# LEDS_DISP.net
KiCad netlist of a schematic drawn in Altium Designer
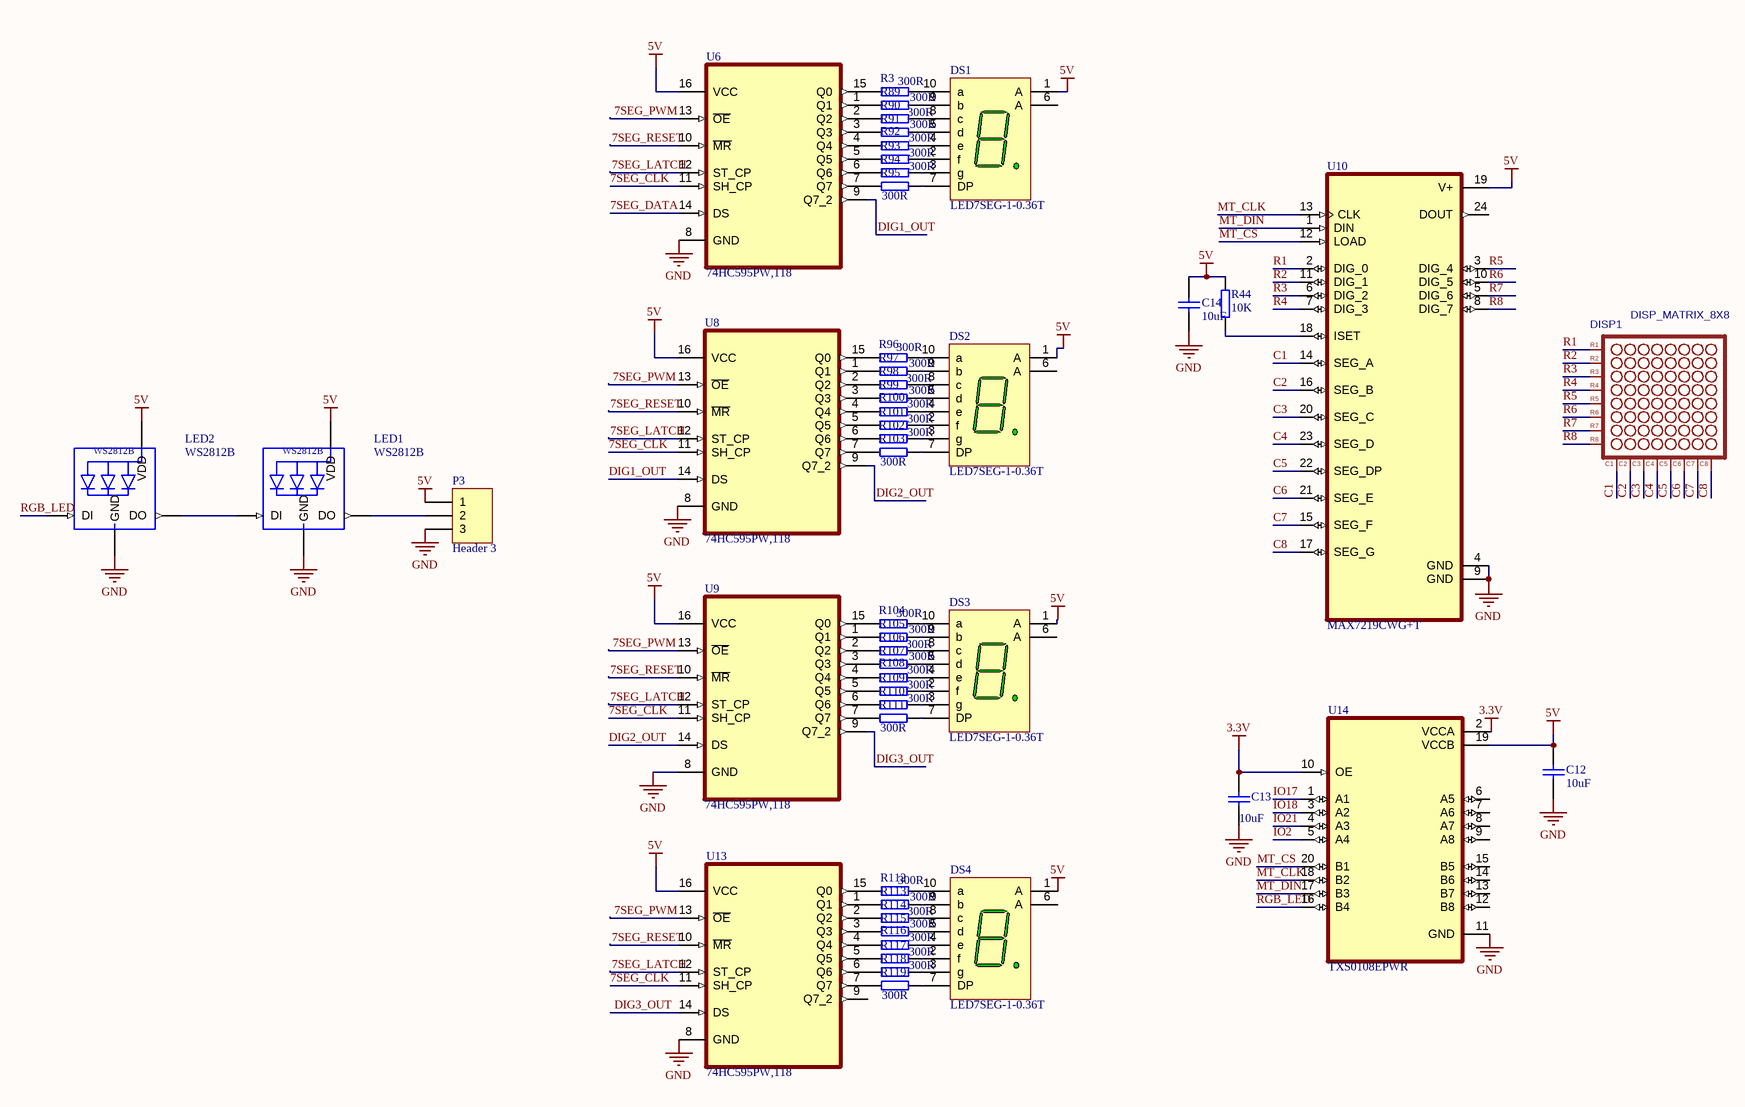
[diagram p0: LEDS_DISP.SchDoc]

(export (version "E")
  (design (tool "Eeschema 10.0.6"))
  (components
    (comp (ref "C12")
      (value "10uF")
      (footprint "CAPC1608X90N")
      (description "CAP SM 0603 X5R 10uF 10%")
      (fields (field (name "TOLERANCE") "±10%") (field (name "Comment") "Cap Semi"))
      (libsource (lib "electronpowered") (part "CAP-SM-0603-X5R-10uF"))
    )
    (comp (ref "C13")
      (value "10uF")
      (footprint "CAPC1608X90N")
      (description "CAP SM 0603 X5R 10uF 10%")
      (fields (field (name "TOLERANCE") "±10%") (field (name "Comment") "Cap Semi"))
      (libsource (lib "electronpowered") (part "CAP-SM-0603-X5R-10uF"))
    )
    (comp (ref "C14")
      (value "10uF")
      (footprint "CAPC1608X90N")
      (description "CAP SM 0603 X5R 10uF 10%")
      (fields (field (name "TOLERANCE") "±10%") (field (name "Comment") "Cap Semi"))
      (libsource (lib "electronpowered") (part "CAP-SM-0603-X5R-10uF"))
    )
    (comp (ref "DISP1")
      (value "DISP_MATRIX_8X8")
      (footprint "DISP_8X8_MATRIX_2020")
      (fields (field (name "BOM_MANUFACTURER PART") "?") (field (name "CONTRIBUTOR") "DangerousPrototype"))
      (libsource (lib "ledmatrix") (part "DISP_MATRIX_8X8"))
    )
    (comp (ref "DS1")
      (value "LED7SEG-1-0.36T")
      (footprint "LED7SEG-1-0.36T")
      (description "7.6 mm Micro Bright Green 7-Segment Display: CA, RH DP")
      (fields (field (name "PUBLISHER") "Altium Limited"))
      (libsource (lib "My Library") (part "LED7SEG-1-0.36T"))
    )
    (comp (ref "DS2")
      (value "LED7SEG-1-0.36T")
      (footprint "LED7SEG-1-0.36T")
      (description "7.6 mm Micro Bright Green 7-Segment Display: CA, RH DP")
      (fields (field (name "PUBLISHER") "Altium Limited"))
      (libsource (lib "My Library") (part "LED7SEG-1-0.36T"))
    )
    (comp (ref "DS3")
      (value "LED7SEG-1-0.36T")
      (footprint "LED7SEG-1-0.36T")
      (description "7.6 mm Micro Bright Green 7-Segment Display: CA, RH DP")
      (fields (field (name "PUBLISHER") "Altium Limited"))
      (libsource (lib "My Library") (part "LED7SEG-1-0.36T"))
    )
    (comp (ref "DS4")
      (value "LED7SEG-1-0.36T")
      (footprint "LED7SEG-1-0.36T")
      (description "7.6 mm Micro Bright Green 7-Segment Display: CA, RH DP")
      (fields (field (name "PUBLISHER") "Altium Limited"))
      (libsource (lib "My Library") (part "LED7SEG-1-0.36T"))
    )
    (comp (ref "LED1")
      (value "WS2812B")
      (footprint "WS2812B")
      (description "Raspberry Pi HAT _40 pin_ Wheeled Robotics Kit")
      (fields (field (name "MF") "SparkFun Electronics"))
      (libsource (lib "WIle_dev_kit") (part "WS2812B"))
    )
    (comp (ref "LED2")
      (value "WS2812B")
      (footprint "WS2812B")
      (description "Raspberry Pi HAT _40 pin_ Wheeled Robotics Kit")
      (fields (field (name "MF") "SparkFun Electronics"))
      (libsource (lib "WIle_dev_kit") (part "WS2812B"))
    )
    (comp (ref "P3")
      (value "Header 3")
      (footprint "HDR1X3")
      (description "Header, 3-Pin")
      (fields (field (name "PUBLISHER") "Altium Limited"))
      (libsource (lib "WIle_dev_kit") (part "Header 3"))
    )
    (comp (ref "R3")
      (value "300R")
      (footprint "RESC1608N_ZERO")
      (description "RES SM 0603 300R")
      (fields (field (name "Comment") "Resistor"))
      (libsource (lib "electronpowered") (part "RES-SM-0603-10K"))
    )
    (comp (ref "R44")
      (value "10K")
      (footprint "RESC1608N_ZERO")
      (description "RES SM 0603 10K")
      (fields (field (name "Comment") "Resistor"))
      (libsource (lib "electronpowered") (part "RES-SM-0603-10K"))
    )
    (comp (ref "R89")
      (value "300R")
      (footprint "RESC1608N_ZERO")
      (description "RES SM 0603 300R")
      (fields (field (name "Comment") "Resistor"))
      (libsource (lib "electronpowered") (part "RES-SM-0603-10K"))
    )
    (comp (ref "R90")
      (value "300R")
      (footprint "RESC1608N_ZERO")
      (description "RES SM 0603 300R")
      (fields (field (name "Comment") "Resistor"))
      (libsource (lib "electronpowered") (part "RES-SM-0603-10K"))
    )
    (comp (ref "R91")
      (value "300R")
      (footprint "RESC1608N_ZERO")
      (description "RES SM 0603 300R")
      (fields (field (name "Comment") "Resistor"))
      (libsource (lib "electronpowered") (part "RES-SM-0603-10K"))
    )
    (comp (ref "R92")
      (value "300R")
      (footprint "RESC1608N_ZERO")
      (description "RES SM 0603 300R")
      (fields (field (name "Comment") "Resistor"))
      (libsource (lib "electronpowered") (part "RES-SM-0603-10K"))
    )
    (comp (ref "R93")
      (value "300R")
      (footprint "RESC1608N_ZERO")
      (description "RES SM 0603 300R")
      (fields (field (name "Comment") "Resistor"))
      (libsource (lib "electronpowered") (part "RES-SM-0603-10K"))
    )
    (comp (ref "R94")
      (value "300R")
      (footprint "RESC1608N_ZERO")
      (description "RES SM 0603 300R")
      (fields (field (name "Comment") "Resistor"))
      (libsource (lib "electronpowered") (part "RES-SM-0603-10K"))
    )
    (comp (ref "R95")
      (value "300R")
      (footprint "RESC1608N_ZERO")
      (description "RES SM 0603 300R")
      (fields (field (name "Comment") "Resistor"))
      (libsource (lib "electronpowered") (part "RES-SM-0603-10K"))
    )
    (comp (ref "R96")
      (value "300R")
      (footprint "RESC1608N_ZERO")
      (description "RES SM 0603 300R")
      (fields (field (name "Comment") "Resistor"))
      (libsource (lib "electronpowered") (part "RES-SM-0603-10K"))
    )
    (comp (ref "R97")
      (value "300R")
      (footprint "RESC1608N_ZERO")
      (description "RES SM 0603 300R")
      (fields (field (name "Comment") "Resistor"))
      (libsource (lib "electronpowered") (part "RES-SM-0603-10K"))
    )
    (comp (ref "R98")
      (value "300R")
      (footprint "RESC1608N_ZERO")
      (description "RES SM 0603 300R")
      (fields (field (name "Comment") "Resistor"))
      (libsource (lib "electronpowered") (part "RES-SM-0603-10K"))
    )
    (comp (ref "R99")
      (value "300R")
      (footprint "RESC1608N_ZERO")
      (description "RES SM 0603 300R")
      (fields (field (name "Comment") "Resistor"))
      (libsource (lib "electronpowered") (part "RES-SM-0603-10K"))
    )
    (comp (ref "R100")
      (value "300R")
      (footprint "RESC1608N_ZERO")
      (description "RES SM 0603 300R")
      (fields (field (name "Comment") "Resistor"))
      (libsource (lib "electronpowered") (part "RES-SM-0603-10K"))
    )
    (comp (ref "R101")
      (value "300R")
      (footprint "RESC1608N_ZERO")
      (description "RES SM 0603 300R")
      (fields (field (name "Comment") "Resistor"))
      (libsource (lib "electronpowered") (part "RES-SM-0603-10K"))
    )
    (comp (ref "R102")
      (value "300R")
      (footprint "RESC1608N_ZERO")
      (description "RES SM 0603 300R")
      (fields (field (name "Comment") "Resistor"))
      (libsource (lib "electronpowered") (part "RES-SM-0603-10K"))
    )
    (comp (ref "R103")
      (value "300R")
      (footprint "RESC1608N_ZERO")
      (description "RES SM 0603 300R")
      (fields (field (name "Comment") "Resistor"))
      (libsource (lib "electronpowered") (part "RES-SM-0603-10K"))
    )
    (comp (ref "R104")
      (value "300R")
      (footprint "RESC1608N_ZERO")
      (description "RES SM 0603 300R")
      (fields (field (name "Comment") "Resistor"))
      (libsource (lib "electronpowered") (part "RES-SM-0603-10K"))
    )
    (comp (ref "R105")
      (value "300R")
      (footprint "RESC1608N_ZERO")
      (description "RES SM 0603 300R")
      (fields (field (name "Comment") "Resistor"))
      (libsource (lib "electronpowered") (part "RES-SM-0603-10K"))
    )
    (comp (ref "R106")
      (value "300R")
      (footprint "RESC1608N_ZERO")
      (description "RES SM 0603 300R")
      (fields (field (name "Comment") "Resistor"))
      (libsource (lib "electronpowered") (part "RES-SM-0603-10K"))
    )
    (comp (ref "R107")
      (value "300R")
      (footprint "RESC1608N_ZERO")
      (description "RES SM 0603 300R")
      (fields (field (name "Comment") "Resistor"))
      (libsource (lib "electronpowered") (part "RES-SM-0603-10K"))
    )
    (comp (ref "R108")
      (value "300R")
      (footprint "RESC1608N_ZERO")
      (description "RES SM 0603 300R")
      (fields (field (name "Comment") "Resistor"))
      (libsource (lib "electronpowered") (part "RES-SM-0603-10K"))
    )
    (comp (ref "R109")
      (value "300R")
      (footprint "RESC1608N_ZERO")
      (description "RES SM 0603 300R")
      (fields (field (name "Comment") "Resistor"))
      (libsource (lib "electronpowered") (part "RES-SM-0603-10K"))
    )
    (comp (ref "R110")
      (value "300R")
      (footprint "RESC1608N_ZERO")
      (description "RES SM 0603 300R")
      (fields (field (name "Comment") "Resistor"))
      (libsource (lib "electronpowered") (part "RES-SM-0603-10K"))
    )
    (comp (ref "R111")
      (value "300R")
      (footprint "RESC1608N_ZERO")
      (description "RES SM 0603 300R")
      (fields (field (name "Comment") "Resistor"))
      (libsource (lib "electronpowered") (part "RES-SM-0603-10K"))
    )
    (comp (ref "R112")
      (value "300R")
      (footprint "RESC1608N_ZERO")
      (description "RES SM 0603 300R")
      (fields (field (name "Comment") "Resistor"))
      (libsource (lib "electronpowered") (part "RES-SM-0603-10K"))
    )
    (comp (ref "R113")
      (value "300R")
      (footprint "RESC1608N_ZERO")
      (description "RES SM 0603 300R")
      (fields (field (name "Comment") "Resistor"))
      (libsource (lib "electronpowered") (part "RES-SM-0603-10K"))
    )
    (comp (ref "R114")
      (value "300R")
      (footprint "RESC1608N_ZERO")
      (description "RES SM 0603 300R")
      (fields (field (name "Comment") "Resistor"))
      (libsource (lib "electronpowered") (part "RES-SM-0603-10K"))
    )
    (comp (ref "R115")
      (value "300R")
      (footprint "RESC1608N_ZERO")
      (description "RES SM 0603 300R")
      (fields (field (name "Comment") "Resistor"))
      (libsource (lib "electronpowered") (part "RES-SM-0603-10K"))
    )
    (comp (ref "R116")
      (value "300R")
      (footprint "RESC1608N_ZERO")
      (description "RES SM 0603 300R")
      (fields (field (name "Comment") "Resistor"))
      (libsource (lib "electronpowered") (part "RES-SM-0603-10K"))
    )
    (comp (ref "R117")
      (value "300R")
      (footprint "RESC1608N_ZERO")
      (description "RES SM 0603 300R")
      (fields (field (name "Comment") "Resistor"))
      (libsource (lib "electronpowered") (part "RES-SM-0603-10K"))
    )
    (comp (ref "R118")
      (value "300R")
      (footprint "RESC1608N_ZERO")
      (description "RES SM 0603 300R")
      (fields (field (name "Comment") "Resistor"))
      (libsource (lib "electronpowered") (part "RES-SM-0603-10K"))
    )
    (comp (ref "R119")
      (value "300R")
      (footprint "RESC1608N_ZERO")
      (description "RES SM 0603 300R")
      (fields (field (name "Comment") "Resistor"))
      (libsource (lib "electronpowered") (part "RES-SM-0603-10K"))
    )
    (comp (ref "U6")
      (value "74HC595PW,118")
      (footprint "SOP65P640X110-16N")
      (description "Shift Shift Register 1 Element 8 Bit 16-TSSOP")
      (fields (field (name "MF") "Nexperia USA"))
      (libsource (lib "74HC595PW_118") (part "74HC595PW,118"))
    )
    (comp (ref "U8")
      (value "74HC595PW,118")
      (footprint "SOP65P640X110-16N")
      (description "Shift Shift Register 1 Element 8 Bit 16-TSSOP")
      (fields (field (name "MF") "Nexperia USA"))
      (libsource (lib "74HC595PW_118") (part "74HC595PW,118"))
    )
    (comp (ref "U9")
      (value "74HC595PW,118")
      (footprint "SOP65P640X110-16N")
      (description "Shift Shift Register 1 Element 8 Bit 16-TSSOP")
      (fields (field (name "MF") "Nexperia USA"))
      (libsource (lib "74HC595PW_118") (part "74HC595PW,118"))
    )
    (comp (ref "U10")
      (value "MAX7219CWG+T")
      (footprint "SOIC127P1032X265-24N")
      (description "LED Driver 64 Segment 330000uA Supply Current 24-Pin SOIC W T/R")
      (fields (field (name "MF") "Maxim Integrated Products"))
      (libsource (lib "MAX7219CWG_T") (part "MAX7219CWG+T"))
    )
    (comp (ref "U13")
      (value "74HC595PW,118")
      (footprint "SOP65P640X110-16N")
      (description "Shift Shift Register 1 Element 8 Bit 16-TSSOP")
      (fields (field (name "MF") "Nexperia USA"))
      (libsource (lib "74HC595PW_118") (part "74HC595PW,118"))
    )
    (comp (ref "U14")
      (value "TXS0108EPWR")
      (footprint "SOP65P640X120-20N")
      (description "8-bit bidirectional voltage-level shifter for open-drain and push-pull application")
      (fields (field (name "MF") "Texas Instruments"))
      (libsource (lib "TXS0108EPWR") (part "TXS0108EPWR"))
    )
  )
  (nets
    (net (code "1") (name "/7SEG_CLK") (class "Default")
      (node (ref "U13") (pin "11") (pinfunction "SH_CP_11") (pintype "input"))
      (node (ref "U6") (pin "11") (pinfunction "SH_CP_11") (pintype "input"))
      (node (ref "U8") (pin "11") (pinfunction "SH_CP_11") (pintype "input"))
      (node (ref "U9") (pin "11") (pinfunction "SH_CP_11") (pintype "input"))
    )
    (net (code "2") (name "/7SEG_DATA") (class "Default")
      (node (ref "U6") (pin "14") (pinfunction "DS_14") (pintype "input"))
    )
    (net (code "3") (name "/7SEG_LATCH") (class "Default")
      (node (ref "U13") (pin "12") (pinfunction "ST_CP_12") (pintype "input"))
      (node (ref "U6") (pin "12") (pinfunction "ST_CP_12") (pintype "input"))
      (node (ref "U8") (pin "12") (pinfunction "ST_CP_12") (pintype "input"))
      (node (ref "U9") (pin "12") (pinfunction "ST_CP_12") (pintype "input"))
    )
    (net (code "4") (name "/7SEG_PWM") (class "Default")
      (node (ref "U13") (pin "13") (pinfunction "~{OE}_13") (pintype "input"))
      (node (ref "U6") (pin "13") (pinfunction "~{OE}_13") (pintype "input"))
      (node (ref "U8") (pin "13") (pinfunction "~{OE}_13") (pintype "input"))
      (node (ref "U9") (pin "13") (pinfunction "~{OE}_13") (pintype "input"))
    )
    (net (code "5") (name "/7SEG_RESET") (class "Default")
      (node (ref "U13") (pin "10") (pinfunction "~{MR}_10") (pintype "input"))
      (node (ref "U6") (pin "10") (pinfunction "~{MR}_10") (pintype "input"))
      (node (ref "U8") (pin "10") (pinfunction "~{MR}_10") (pintype "input"))
      (node (ref "U9") (pin "10") (pinfunction "~{MR}_10") (pintype "input"))
    )
    (net (code "6") (name "/C1") (class "Default")
      (node (ref "DISP1") (pin "13") (pinfunction "C1_13") (pintype "passive"))
      (node (ref "U10") (pin "14") (pinfunction "SEG_A_14") (pintype "bidirectional"))
    )
    (net (code "7") (name "/C2") (class "Default")
      (node (ref "DISP1") (pin "3") (pinfunction "C2_3") (pintype "passive"))
      (node (ref "U10") (pin "16") (pinfunction "SEG_B_16") (pintype "bidirectional"))
    )
    (net (code "8") (name "/C3") (class "Default")
      (node (ref "DISP1") (pin "4") (pinfunction "C3_4") (pintype "passive"))
      (node (ref "U10") (pin "20") (pinfunction "SEG_C_20") (pintype "bidirectional"))
    )
    (net (code "9") (name "/C4") (class "Default")
      (node (ref "DISP1") (pin "10") (pinfunction "C4_10") (pintype "passive"))
      (node (ref "U10") (pin "23") (pinfunction "SEG_D_23") (pintype "bidirectional"))
    )
    (net (code "10") (name "/C5") (class "Default")
      (node (ref "DISP1") (pin "6") (pinfunction "C5_6") (pintype "passive"))
      (node (ref "U10") (pin "22") (pinfunction "SEG_DP_22") (pintype "bidirectional"))
    )
    (net (code "11") (name "/C6") (class "Default")
      (node (ref "DISP1") (pin "11") (pinfunction "C6_11") (pintype "passive"))
      (node (ref "U10") (pin "21") (pinfunction "SEG_E_21") (pintype "bidirectional"))
    )
    (net (code "12") (name "/C7") (class "Default")
      (node (ref "DISP1") (pin "15") (pinfunction "C7_15") (pintype "passive"))
      (node (ref "U10") (pin "15") (pinfunction "SEG_F_15") (pintype "bidirectional"))
    )
    (net (code "13") (name "/C8") (class "Default")
      (node (ref "DISP1") (pin "16") (pinfunction "C8_16") (pintype "passive"))
      (node (ref "U10") (pin "17") (pinfunction "SEG_G_17") (pintype "bidirectional"))
    )
    (net (code "14") (name "/DIG1_OUT") (class "Default")
      (node (ref "U6") (pin "9") (pinfunction "Q7_2_9") (pintype "output"))
      (node (ref "U8") (pin "14") (pinfunction "DS_14") (pintype "input"))
    )
    (net (code "15") (name "/DIG2_OUT") (class "Default")
      (node (ref "U8") (pin "9") (pinfunction "Q7_2_9") (pintype "output"))
      (node (ref "U9") (pin "14") (pinfunction "DS_14") (pintype "input"))
    )
    (net (code "16") (name "/DIG3_OUT") (class "Default")
      (node (ref "U13") (pin "14") (pinfunction "DS_14") (pintype "input"))
      (node (ref "U9") (pin "9") (pinfunction "Q7_2_9") (pintype "output"))
    )
    (net (code "17") (name "/IO2") (class "Default")
      (node (ref "U14") (pin "5") (pinfunction "A4_5") (pintype "bidirectional"))
    )
    (net (code "18") (name "/IO17") (class "Default")
      (node (ref "U14") (pin "1") (pinfunction "A1_1") (pintype "bidirectional"))
    )
    (net (code "19") (name "/IO18") (class "Default")
      (node (ref "U14") (pin "3") (pinfunction "A2_3") (pintype "bidirectional"))
    )
    (net (code "20") (name "/IO21") (class "Default")
      (node (ref "U14") (pin "4") (pinfunction "A3_4") (pintype "bidirectional"))
    )
    (net (code "21") (name "/MT_CLK") (class "Default")
      (node (ref "U10") (pin "13") (pinfunction "CLK_13") (pintype "input"))
      (node (ref "U14") (pin "18") (pinfunction "B2_18") (pintype "bidirectional"))
    )
    (net (code "22") (name "/MT_CS") (class "Default")
      (node (ref "U10") (pin "12") (pinfunction "LOAD_12") (pintype "input"))
      (node (ref "U14") (pin "20") (pinfunction "B1_20") (pintype "bidirectional"))
    )
    (net (code "23") (name "/MT_DIN") (class "Default")
      (node (ref "U10") (pin "1") (pinfunction "DIN_1") (pintype "input"))
      (node (ref "U14") (pin "17") (pinfunction "B3_17") (pintype "bidirectional"))
    )
    (net (code "24") (name "/R1") (class "Default")
      (node (ref "DISP1") (pin "9") (pinfunction "R1_9") (pintype "passive"))
      (node (ref "U10") (pin "2") (pinfunction "DIG_0_2") (pintype "bidirectional"))
    )
    (net (code "25") (name "/R2") (class "Default")
      (node (ref "DISP1") (pin "14") (pinfunction "R2_14") (pintype "passive"))
      (node (ref "U10") (pin "11") (pinfunction "DIG_1_11") (pintype "bidirectional"))
    )
    (net (code "26") (name "/R3") (class "Default")
      (node (ref "DISP1") (pin "8") (pinfunction "R3_8") (pintype "passive"))
      (node (ref "U10") (pin "6") (pinfunction "DIG_2_6") (pintype "bidirectional"))
    )
    (net (code "27") (name "/R4") (class "Default")
      (node (ref "DISP1") (pin "12") (pinfunction "R4_12") (pintype "passive"))
      (node (ref "U10") (pin "7") (pinfunction "DIG_3_7") (pintype "bidirectional"))
    )
    (net (code "28") (name "/R5") (class "Default")
      (node (ref "DISP1") (pin "1") (pinfunction "R5_1") (pintype "passive"))
      (node (ref "U10") (pin "3") (pinfunction "DIG_4_3") (pintype "bidirectional"))
    )
    (net (code "29") (name "/R6") (class "Default")
      (node (ref "DISP1") (pin "7") (pinfunction "R6_7") (pintype "passive"))
      (node (ref "U10") (pin "10") (pinfunction "DIG_5_10") (pintype "bidirectional"))
    )
    (net (code "30") (name "/R7") (class "Default")
      (node (ref "DISP1") (pin "2") (pinfunction "R7_2") (pintype "passive"))
      (node (ref "U10") (pin "5") (pinfunction "DIG_6_5") (pintype "bidirectional"))
    )
    (net (code "31") (name "/R8") (class "Default")
      (node (ref "DISP1") (pin "5") (pinfunction "R8_5") (pintype "passive"))
      (node (ref "U10") (pin "8") (pinfunction "DIG_7_8") (pintype "bidirectional"))
    )
    (net (code "32") (name "/RGB_LED") (class "Default")
      (node (ref "LED2") (pin "4-DIN") (pinfunction "DI_4-DIN") (pintype "input"))
      (node (ref "U14") (pin "16") (pinfunction "B4_16") (pintype "bidirectional"))
    )
    (net (code "33") (name "3.3V") (class "Default")
      (node (ref "C13") (pin "2") (pinfunction "2_2") (pintype "passive"))
      (node (ref "U14") (pin "10") (pinfunction "OE_10") (pintype "input"))
      (node (ref "U14") (pin "2") (pinfunction "VCCA_2") (pintype "power_in"))
    )
    (net (code "34") (name "5V") (class "Default")
      (node (ref "C12") (pin "1") (pinfunction "1_1") (pintype "passive"))
      (node (ref "C14") (pin "1") (pinfunction "1_1") (pintype "passive"))
      (node (ref "DS1") (pin "1") (pinfunction "A_1") (pintype "passive"))
      (node (ref "DS2") (pin "1") (pinfunction "A_1") (pintype "passive"))
      (node (ref "DS3") (pin "1") (pinfunction "A_1") (pintype "passive"))
      (node (ref "DS4") (pin "1") (pinfunction "A_1") (pintype "passive"))
      (node (ref "LED1") (pin "1-VDD") (pinfunction "VDD_1-VDD") (pintype "power_in"))
      (node (ref "LED2") (pin "1-VDD") (pinfunction "VDD_1-VDD") (pintype "power_in"))
      (node (ref "P3") (pin "1") (pinfunction "1_1") (pintype "passive"))
      (node (ref "R44") (pin "1") (pinfunction "1_1") (pintype "passive"))
      (node (ref "U10") (pin "19") (pinfunction "V+_19") (pintype "power_in"))
      (node (ref "U13") (pin "16") (pinfunction "VCC_16") (pintype "power_in"))
      (node (ref "U14") (pin "19") (pinfunction "VCCB_19") (pintype "power_in"))
      (node (ref "U6") (pin "16") (pinfunction "VCC_16") (pintype "power_in"))
      (node (ref "U8") (pin "16") (pinfunction "VCC_16") (pintype "power_in"))
      (node (ref "U9") (pin "16") (pinfunction "VCC_16") (pintype "power_in"))
    )
    (net (code "35") (name "GND") (class "Default")
      (node (ref "C12") (pin "2") (pinfunction "2_2") (pintype "passive"))
      (node (ref "C13") (pin "1") (pinfunction "1_1") (pintype "passive"))
      (node (ref "C14") (pin "2") (pinfunction "2_2") (pintype "passive"))
      (node (ref "LED1") (pin "3-GND") (pinfunction "GND_3-GND") (pintype "power_in"))
      (node (ref "LED2") (pin "3-GND") (pinfunction "GND_3-GND") (pintype "power_in"))
      (node (ref "P3") (pin "3") (pinfunction "3_3") (pintype "passive"))
      (node (ref "U10") (pin "4") (pinfunction "GND_4") (pintype "power_in"))
      (node (ref "U10") (pin "9") (pinfunction "GND_9") (pintype "power_in"))
      (node (ref "U13") (pin "8") (pinfunction "GND_8") (pintype "passive"))
      (node (ref "U14") (pin "11") (pinfunction "GND_11") (pintype "power_in"))
      (node (ref "U6") (pin "8") (pinfunction "GND_8") (pintype "passive"))
      (node (ref "U8") (pin "8") (pinfunction "GND_8") (pintype "passive"))
      (node (ref "U9") (pin "8") (pinfunction "GND_8") (pintype "passive"))
    )
    (net (code "36") (name "Net-(DS1-DP)") (class "Default")
      (node (ref "DS1") (pin "7") (pinfunction "DP_7") (pintype "passive"))
      (node (ref "R95") (pin "1") (pinfunction "1_1") (pintype "passive"))
    )
    (net (code "37") (name "Net-(DS1-a)") (class "Default")
      (node (ref "DS1") (pin "10") (pinfunction "a_10") (pintype "passive"))
      (node (ref "R3") (pin "1") (pinfunction "1_1") (pintype "passive"))
    )
    (net (code "38") (name "Net-(DS1-b)") (class "Default")
      (node (ref "DS1") (pin "9") (pinfunction "b_9") (pintype "passive"))
      (node (ref "R89") (pin "1") (pinfunction "1_1") (pintype "passive"))
    )
    (net (code "39") (name "Net-(DS1-c)") (class "Default")
      (node (ref "DS1") (pin "8") (pinfunction "c_8") (pintype "passive"))
      (node (ref "R90") (pin "1") (pinfunction "1_1") (pintype "passive"))
    )
    (net (code "40") (name "Net-(DS1-d)") (class "Default")
      (node (ref "DS1") (pin "5") (pinfunction "d_5") (pintype "passive"))
      (node (ref "R91") (pin "1") (pinfunction "1_1") (pintype "passive"))
    )
    (net (code "41") (name "Net-(DS1-e)") (class "Default")
      (node (ref "DS1") (pin "4") (pinfunction "e_4") (pintype "passive"))
      (node (ref "R92") (pin "1") (pinfunction "1_1") (pintype "passive"))
    )
    (net (code "42") (name "Net-(DS1-f)") (class "Default")
      (node (ref "DS1") (pin "2") (pinfunction "f_2") (pintype "passive"))
      (node (ref "R93") (pin "1") (pinfunction "1_1") (pintype "passive"))
    )
    (net (code "43") (name "Net-(DS1-g)") (class "Default")
      (node (ref "DS1") (pin "3") (pinfunction "g_3") (pintype "passive"))
      (node (ref "R94") (pin "1") (pinfunction "1_1") (pintype "passive"))
    )
    (net (code "44") (name "Net-(DS2-DP)") (class "Default")
      (node (ref "DS2") (pin "7") (pinfunction "DP_7") (pintype "passive"))
      (node (ref "R103") (pin "1") (pinfunction "1_1") (pintype "passive"))
    )
    (net (code "45") (name "Net-(DS2-a)") (class "Default")
      (node (ref "DS2") (pin "10") (pinfunction "a_10") (pintype "passive"))
      (node (ref "R96") (pin "1") (pinfunction "1_1") (pintype "passive"))
    )
    (net (code "46") (name "Net-(DS2-b)") (class "Default")
      (node (ref "DS2") (pin "9") (pinfunction "b_9") (pintype "passive"))
      (node (ref "R97") (pin "1") (pinfunction "1_1") (pintype "passive"))
    )
    (net (code "47") (name "Net-(DS2-c)") (class "Default")
      (node (ref "DS2") (pin "8") (pinfunction "c_8") (pintype "passive"))
      (node (ref "R98") (pin "1") (pinfunction "1_1") (pintype "passive"))
    )
    (net (code "48") (name "Net-(DS2-d)") (class "Default")
      (node (ref "DS2") (pin "5") (pinfunction "d_5") (pintype "passive"))
      (node (ref "R99") (pin "1") (pinfunction "1_1") (pintype "passive"))
    )
    (net (code "49") (name "Net-(DS2-e)") (class "Default")
      (node (ref "DS2") (pin "4") (pinfunction "e_4") (pintype "passive"))
      (node (ref "R100") (pin "1") (pinfunction "1_1") (pintype "passive"))
    )
    (net (code "50") (name "Net-(DS2-f)") (class "Default")
      (node (ref "DS2") (pin "2") (pinfunction "f_2") (pintype "passive"))
      (node (ref "R101") (pin "1") (pinfunction "1_1") (pintype "passive"))
    )
    (net (code "51") (name "Net-(DS2-g)") (class "Default")
      (node (ref "DS2") (pin "3") (pinfunction "g_3") (pintype "passive"))
      (node (ref "R102") (pin "1") (pinfunction "1_1") (pintype "passive"))
    )
    (net (code "52") (name "Net-(DS3-DP)") (class "Default")
      (node (ref "DS3") (pin "7") (pinfunction "DP_7") (pintype "passive"))
      (node (ref "R111") (pin "1") (pinfunction "1_1") (pintype "passive"))
    )
    (net (code "53") (name "Net-(DS3-a)") (class "Default")
      (node (ref "DS3") (pin "10") (pinfunction "a_10") (pintype "passive"))
      (node (ref "R104") (pin "1") (pinfunction "1_1") (pintype "passive"))
    )
    (net (code "54") (name "Net-(DS3-b)") (class "Default")
      (node (ref "DS3") (pin "9") (pinfunction "b_9") (pintype "passive"))
      (node (ref "R105") (pin "1") (pinfunction "1_1") (pintype "passive"))
    )
    (net (code "55") (name "Net-(DS3-c)") (class "Default")
      (node (ref "DS3") (pin "8") (pinfunction "c_8") (pintype "passive"))
      (node (ref "R106") (pin "1") (pinfunction "1_1") (pintype "passive"))
    )
    (net (code "56") (name "Net-(DS3-d)") (class "Default")
      (node (ref "DS3") (pin "5") (pinfunction "d_5") (pintype "passive"))
      (node (ref "R107") (pin "1") (pinfunction "1_1") (pintype "passive"))
    )
    (net (code "57") (name "Net-(DS3-e)") (class "Default")
      (node (ref "DS3") (pin "4") (pinfunction "e_4") (pintype "passive"))
      (node (ref "R108") (pin "1") (pinfunction "1_1") (pintype "passive"))
    )
    (net (code "58") (name "Net-(DS3-f)") (class "Default")
      (node (ref "DS3") (pin "2") (pinfunction "f_2") (pintype "passive"))
      (node (ref "R109") (pin "1") (pinfunction "1_1") (pintype "passive"))
    )
    (net (code "59") (name "Net-(DS3-g)") (class "Default")
      (node (ref "DS3") (pin "3") (pinfunction "g_3") (pintype "passive"))
      (node (ref "R110") (pin "1") (pinfunction "1_1") (pintype "passive"))
    )
    (net (code "60") (name "Net-(DS4-DP)") (class "Default")
      (node (ref "DS4") (pin "7") (pinfunction "DP_7") (pintype "passive"))
      (node (ref "R119") (pin "1") (pinfunction "1_1") (pintype "passive"))
    )
    (net (code "61") (name "Net-(DS4-a)") (class "Default")
      (node (ref "DS4") (pin "10") (pinfunction "a_10") (pintype "passive"))
      (node (ref "R112") (pin "1") (pinfunction "1_1") (pintype "passive"))
    )
    (net (code "62") (name "Net-(DS4-b)") (class "Default")
      (node (ref "DS4") (pin "9") (pinfunction "b_9") (pintype "passive"))
      (node (ref "R113") (pin "1") (pinfunction "1_1") (pintype "passive"))
    )
    (net (code "63") (name "Net-(DS4-c)") (class "Default")
      (node (ref "DS4") (pin "8") (pinfunction "c_8") (pintype "passive"))
      (node (ref "R114") (pin "1") (pinfunction "1_1") (pintype "passive"))
    )
    (net (code "64") (name "Net-(DS4-d)") (class "Default")
      (node (ref "DS4") (pin "5") (pinfunction "d_5") (pintype "passive"))
      (node (ref "R115") (pin "1") (pinfunction "1_1") (pintype "passive"))
    )
    (net (code "65") (name "Net-(DS4-e)") (class "Default")
      (node (ref "DS4") (pin "4") (pinfunction "e_4") (pintype "passive"))
      (node (ref "R116") (pin "1") (pinfunction "1_1") (pintype "passive"))
    )
    (net (code "66") (name "Net-(DS4-f)") (class "Default")
      (node (ref "DS4") (pin "2") (pinfunction "f_2") (pintype "passive"))
      (node (ref "R117") (pin "1") (pinfunction "1_1") (pintype "passive"))
    )
    (net (code "67") (name "Net-(DS4-g)") (class "Default")
      (node (ref "DS4") (pin "3") (pinfunction "g_3") (pintype "passive"))
      (node (ref "R118") (pin "1") (pinfunction "1_1") (pintype "passive"))
    )
    (net (code "68") (name "Net-(LED1-DI)") (class "Default")
      (node (ref "LED1") (pin "4-DIN") (pinfunction "DI_4-DIN") (pintype "input"))
      (node (ref "LED2") (pin "2-DOUT") (pinfunction "DO_2-DOUT") (pintype "output"))
    )
    (net (code "69") (name "Net-(LED1-DO)") (class "Default")
      (node (ref "LED1") (pin "2-DOUT") (pinfunction "DO_2-DOUT") (pintype "output"))
      (node (ref "P3") (pin "2") (pinfunction "2_2") (pintype "passive"))
    )
    (net (code "70") (name "Net-(U6-Q0)") (class "Default")
      (node (ref "R3") (pin "2") (pinfunction "2_2") (pintype "passive"))
      (node (ref "U6") (pin "15") (pinfunction "Q0_15") (pintype "output"))
    )
    (net (code "71") (name "Net-(U6-Q1)") (class "Default")
      (node (ref "R89") (pin "2") (pinfunction "2_2") (pintype "passive"))
      (node (ref "U6") (pin "1") (pinfunction "Q1_1") (pintype "output"))
    )
    (net (code "72") (name "Net-(U6-Q2)") (class "Default")
      (node (ref "R90") (pin "2") (pinfunction "2_2") (pintype "passive"))
      (node (ref "U6") (pin "2") (pinfunction "Q2_2") (pintype "output"))
    )
    (net (code "73") (name "Net-(U6-Q3)") (class "Default")
      (node (ref "R91") (pin "2") (pinfunction "2_2") (pintype "passive"))
      (node (ref "U6") (pin "3") (pinfunction "Q3_3") (pintype "output"))
    )
    (net (code "74") (name "Net-(U6-Q4)") (class "Default")
      (node (ref "R92") (pin "2") (pinfunction "2_2") (pintype "passive"))
      (node (ref "U6") (pin "4") (pinfunction "Q4_4") (pintype "output"))
    )
    (net (code "75") (name "Net-(U6-Q5)") (class "Default")
      (node (ref "R93") (pin "2") (pinfunction "2_2") (pintype "passive"))
      (node (ref "U6") (pin "5") (pinfunction "Q5_5") (pintype "output"))
    )
    (net (code "76") (name "Net-(U6-Q6)") (class "Default")
      (node (ref "R94") (pin "2") (pinfunction "2_2") (pintype "passive"))
      (node (ref "U6") (pin "6") (pinfunction "Q6_6") (pintype "output"))
    )
    (net (code "77") (name "Net-(U6-Q7)") (class "Default")
      (node (ref "R95") (pin "2") (pinfunction "2_2") (pintype "passive"))
      (node (ref "U6") (pin "7") (pinfunction "Q7_7") (pintype "output"))
    )
    (net (code "78") (name "Net-(U8-Q0)") (class "Default")
      (node (ref "R96") (pin "2") (pinfunction "2_2") (pintype "passive"))
      (node (ref "U8") (pin "15") (pinfunction "Q0_15") (pintype "output"))
    )
    (net (code "79") (name "Net-(U8-Q1)") (class "Default")
      (node (ref "R97") (pin "2") (pinfunction "2_2") (pintype "passive"))
      (node (ref "U8") (pin "1") (pinfunction "Q1_1") (pintype "output"))
    )
    (net (code "80") (name "Net-(U8-Q2)") (class "Default")
      (node (ref "R98") (pin "2") (pinfunction "2_2") (pintype "passive"))
      (node (ref "U8") (pin "2") (pinfunction "Q2_2") (pintype "output"))
    )
    (net (code "81") (name "Net-(U8-Q3)") (class "Default")
      (node (ref "R99") (pin "2") (pinfunction "2_2") (pintype "passive"))
      (node (ref "U8") (pin "3") (pinfunction "Q3_3") (pintype "output"))
    )
    (net (code "82") (name "Net-(U8-Q4)") (class "Default")
      (node (ref "R100") (pin "2") (pinfunction "2_2") (pintype "passive"))
      (node (ref "U8") (pin "4") (pinfunction "Q4_4") (pintype "output"))
    )
    (net (code "83") (name "Net-(U8-Q5)") (class "Default")
      (node (ref "R101") (pin "2") (pinfunction "2_2") (pintype "passive"))
      (node (ref "U8") (pin "5") (pinfunction "Q5_5") (pintype "output"))
    )
    (net (code "84") (name "Net-(U8-Q6)") (class "Default")
      (node (ref "R102") (pin "2") (pinfunction "2_2") (pintype "passive"))
      (node (ref "U8") (pin "6") (pinfunction "Q6_6") (pintype "output"))
    )
    (net (code "85") (name "Net-(U8-Q7)") (class "Default")
      (node (ref "R103") (pin "2") (pinfunction "2_2") (pintype "passive"))
      (node (ref "U8") (pin "7") (pinfunction "Q7_7") (pintype "output"))
    )
    (net (code "86") (name "Net-(U9-Q0)") (class "Default")
      (node (ref "R104") (pin "2") (pinfunction "2_2") (pintype "passive"))
      (node (ref "U9") (pin "15") (pinfunction "Q0_15") (pintype "output"))
    )
    (net (code "87") (name "Net-(U9-Q1)") (class "Default")
      (node (ref "R105") (pin "2") (pinfunction "2_2") (pintype "passive"))
      (node (ref "U9") (pin "1") (pinfunction "Q1_1") (pintype "output"))
    )
    (net (code "88") (name "Net-(U9-Q2)") (class "Default")
      (node (ref "R106") (pin "2") (pinfunction "2_2") (pintype "passive"))
      (node (ref "U9") (pin "2") (pinfunction "Q2_2") (pintype "output"))
    )
    (net (code "89") (name "Net-(U9-Q3)") (class "Default")
      (node (ref "R107") (pin "2") (pinfunction "2_2") (pintype "passive"))
      (node (ref "U9") (pin "3") (pinfunction "Q3_3") (pintype "output"))
    )
    (net (code "90") (name "Net-(U9-Q4)") (class "Default")
      (node (ref "R108") (pin "2") (pinfunction "2_2") (pintype "passive"))
      (node (ref "U9") (pin "4") (pinfunction "Q4_4") (pintype "output"))
    )
    (net (code "91") (name "Net-(U9-Q5)") (class "Default")
      (node (ref "R109") (pin "2") (pinfunction "2_2") (pintype "passive"))
      (node (ref "U9") (pin "5") (pinfunction "Q5_5") (pintype "output"))
    )
    (net (code "92") (name "Net-(U9-Q6)") (class "Default")
      (node (ref "R110") (pin "2") (pinfunction "2_2") (pintype "passive"))
      (node (ref "U9") (pin "6") (pinfunction "Q6_6") (pintype "output"))
    )
    (net (code "93") (name "Net-(U9-Q7)") (class "Default")
      (node (ref "R111") (pin "2") (pinfunction "2_2") (pintype "passive"))
      (node (ref "U9") (pin "7") (pinfunction "Q7_7") (pintype "output"))
    )
    (net (code "94") (name "Net-(U10-ISET)") (class "Default")
      (node (ref "R44") (pin "2") (pinfunction "2_2") (pintype "passive"))
      (node (ref "U10") (pin "18") (pinfunction "ISET_18") (pintype "bidirectional"))
    )
    (net (code "95") (name "Net-(U13-Q0)") (class "Default")
      (node (ref "R112") (pin "2") (pinfunction "2_2") (pintype "passive"))
      (node (ref "U13") (pin "15") (pinfunction "Q0_15") (pintype "output"))
    )
    (net (code "96") (name "Net-(U13-Q1)") (class "Default")
      (node (ref "R113") (pin "2") (pinfunction "2_2") (pintype "passive"))
      (node (ref "U13") (pin "1") (pinfunction "Q1_1") (pintype "output"))
    )
    (net (code "97") (name "Net-(U13-Q2)") (class "Default")
      (node (ref "R114") (pin "2") (pinfunction "2_2") (pintype "passive"))
      (node (ref "U13") (pin "2") (pinfunction "Q2_2") (pintype "output"))
    )
    (net (code "98") (name "Net-(U13-Q3)") (class "Default")
      (node (ref "R115") (pin "2") (pinfunction "2_2") (pintype "passive"))
      (node (ref "U13") (pin "3") (pinfunction "Q3_3") (pintype "output"))
    )
    (net (code "99") (name "Net-(U13-Q4)") (class "Default")
      (node (ref "R116") (pin "2") (pinfunction "2_2") (pintype "passive"))
      (node (ref "U13") (pin "4") (pinfunction "Q4_4") (pintype "output"))
    )
    (net (code "100") (name "Net-(U13-Q5)") (class "Default")
      (node (ref "R117") (pin "2") (pinfunction "2_2") (pintype "passive"))
      (node (ref "U13") (pin "5") (pinfunction "Q5_5") (pintype "output"))
    )
    (net (code "101") (name "Net-(U13-Q6)") (class "Default")
      (node (ref "R118") (pin "2") (pinfunction "2_2") (pintype "passive"))
      (node (ref "U13") (pin "6") (pinfunction "Q6_6") (pintype "output"))
    )
    (net (code "102") (name "Net-(U13-Q7)") (class "Default")
      (node (ref "R119") (pin "2") (pinfunction "2_2") (pintype "passive"))
      (node (ref "U13") (pin "7") (pinfunction "Q7_7") (pintype "output"))
    )
    (net (code "103") (name "unconnected-(DS1-A-Pad6)") (class "Default")
      (node (ref "DS1") (pin "6") (pinfunction "A_6") (pintype "passive"))
    )
    (net (code "104") (name "unconnected-(DS2-A-Pad6)") (class "Default")
      (node (ref "DS2") (pin "6") (pinfunction "A_6") (pintype "passive"))
    )
    (net (code "105") (name "unconnected-(DS3-A-Pad6)") (class "Default")
      (node (ref "DS3") (pin "6") (pinfunction "A_6") (pintype "passive"))
    )
    (net (code "106") (name "unconnected-(DS4-A-Pad6)") (class "Default")
      (node (ref "DS4") (pin "6") (pinfunction "A_6") (pintype "passive"))
    )
    (net (code "107") (name "unconnected-(U10-DOUT-Pad24)") (class "Default")
      (node (ref "U10") (pin "24") (pinfunction "DOUT_24") (pintype "output"))
    )
    (net (code "108") (name "unconnected-(U13-Q7_2-Pad9)") (class "Default")
      (node (ref "U13") (pin "9") (pinfunction "Q7_2_9") (pintype "output"))
    )
    (net (code "109") (name "unconnected-(U14-A5-Pad6)") (class "Default")
      (node (ref "U14") (pin "6") (pinfunction "A5_6") (pintype "bidirectional"))
    )
    (net (code "110") (name "unconnected-(U14-A6-Pad7)") (class "Default")
      (node (ref "U14") (pin "7") (pinfunction "A6_7") (pintype "bidirectional"))
    )
    (net (code "111") (name "unconnected-(U14-A7-Pad8)") (class "Default")
      (node (ref "U14") (pin "8") (pinfunction "A7_8") (pintype "bidirectional"))
    )
    (net (code "112") (name "unconnected-(U14-A8-Pad9)") (class "Default")
      (node (ref "U14") (pin "9") (pinfunction "A8_9") (pintype "bidirectional"))
    )
    (net (code "113") (name "unconnected-(U14-B5-Pad15)") (class "Default")
      (node (ref "U14") (pin "15") (pinfunction "B5_15") (pintype "bidirectional"))
    )
    (net (code "114") (name "unconnected-(U14-B6-Pad14)") (class "Default")
      (node (ref "U14") (pin "14") (pinfunction "B6_14") (pintype "bidirectional"))
    )
    (net (code "115") (name "unconnected-(U14-B7-Pad13)") (class "Default")
      (node (ref "U14") (pin "13") (pinfunction "B7_13") (pintype "bidirectional"))
    )
    (net (code "116") (name "unconnected-(U14-B8-Pad12)") (class "Default")
      (node (ref "U14") (pin "12") (pinfunction "B8_12") (pintype "bidirectional"))
    )
  )
)
